# LevelShifting_Isolation.net
KiCad netlist of a schematic drawn in Altium Designer
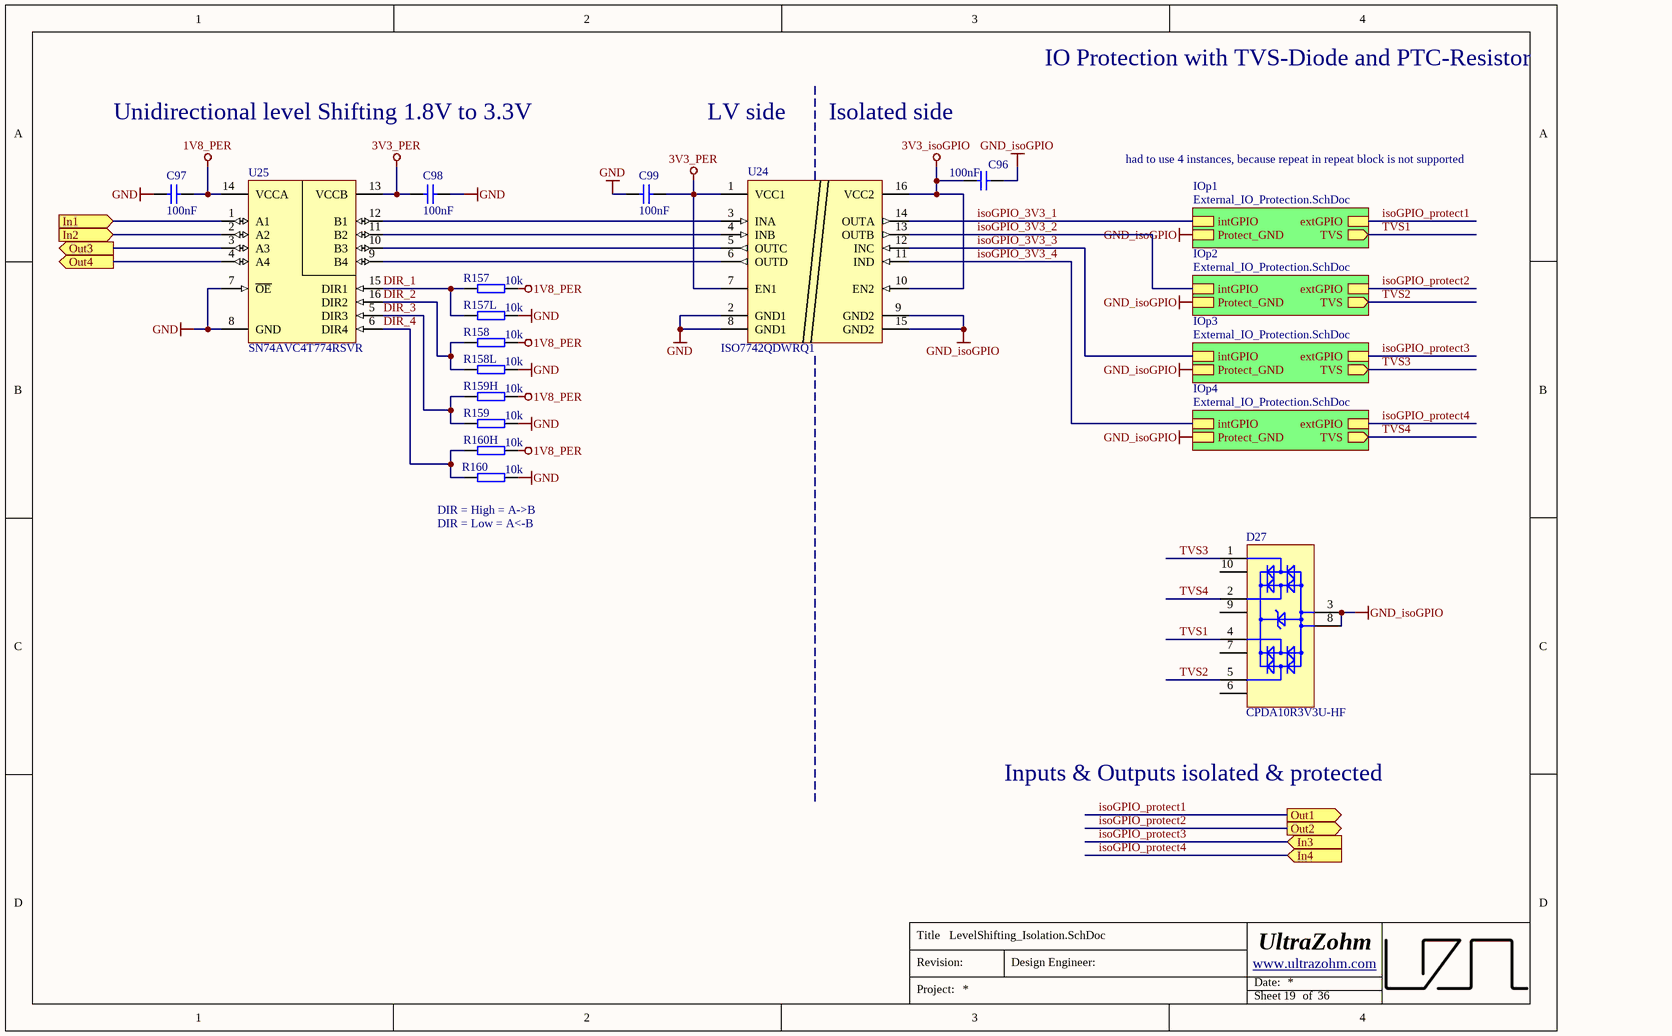
[diagram p0: LevelShifting_Isolation.SchDoc]

(export (version "E")
  (design (tool "Eeschema 10.0.6"))
  (components
    (comp (ref "C96")
      (value "100nF")
      (footprint "CAPC1608X90N_V")
      (description "KON 100nF 50V X7R ±10% SMD BF 1608 (0603)")
      (fields (field (name "TOLERANCE") "±10%") (field (name "VOLTAGE") "50V"))
      (libsource (lib "TE") (part "CAP-NP"))
    )
    (comp (ref "C97")
      (value "100nF")
      (footprint "CAPC1608X90N_V")
      (description "KON 100nF 50V X7R ±10% SMD BF 1608 (0603)")
      (fields (field (name "TOLERANCE") "±10%") (field (name "VOLTAGE") "50V"))
      (libsource (lib "TE") (part "CAP-NP"))
    )
    (comp (ref "C98")
      (value "100nF")
      (footprint "CAPC1608X90N_V")
      (description "KON 100nF 50V X7R ±10% SMD BF 1608 (0603)")
      (fields (field (name "TOLERANCE") "±10%") (field (name "VOLTAGE") "50V"))
      (libsource (lib "TE") (part "CAP-NP"))
    )
    (comp (ref "C99")
      (value "100nF")
      (footprint "CAPC1608X90N_V")
      (description "KON 100nF 50V X7R ±10% SMD BF 1608 (0603)")
      (fields (field (name "TOLERANCE") "±10%") (field (name "VOLTAGE") "50V"))
      (libsource (lib "TE") (part "CAP-NP"))
    )
    (comp (ref "D27")
      (value "CPDA10R3V3U-HF")
      (footprint "DFN230X100X55X10N")
      (fields (field (name "VOLTAGE") "3.3V"))
      (libsource (lib "TE") (part "DIODE_ARR_10N_1"))
    )
    (comp (ref "R157")
      (value "10k")
      (footprint "R_0603_TE")
      (description "Generic resistor")
      (fields
        (field (name "TOLERANCE") "1 %")
        (field (name "MANUFACTURER PART NUMBER") "UZgen_R_0603_10k")
        (field (name "CREATED FROM") "AGeiger")
      )
      (libsource (lib "user") (part "RES"))
    )
    (comp (ref "R157L")
      (value "10k")
      (footprint "R_0603_TE")
      (description "Generic resistor")
      (fields
        (field (name "TOLERANCE") "1 %")
        (field (name "MANUFACTURER PART NUMBER") "UZgen_R_0603_10k")
        (field (name "CREATED FROM") "AGeiger")
      )
      (libsource (lib "user") (part "RES"))
    )
    (comp (ref "R158")
      (value "10k")
      (footprint "R_0603_TE")
      (description "Generic resistor")
      (fields
        (field (name "TOLERANCE") "1 %")
        (field (name "MANUFACTURER PART NUMBER") "UZgen_R_0603_10k")
        (field (name "CREATED FROM") "AGeiger")
      )
      (libsource (lib "user") (part "RES"))
    )
    (comp (ref "R158L")
      (value "10k")
      (footprint "R_0603_TE")
      (description "Generic resistor")
      (fields
        (field (name "TOLERANCE") "1 %")
        (field (name "MANUFACTURER PART NUMBER") "UZgen_R_0603_10k")
        (field (name "CREATED FROM") "AGeiger")
      )
      (libsource (lib "user") (part "RES"))
    )
    (comp (ref "R159")
      (value "10k")
      (footprint "R_0603_TE")
      (description "Generic resistor")
      (fields
        (field (name "TOLERANCE") "1 %")
        (field (name "MANUFACTURER PART NUMBER") "UZgen_R_0603_10k")
        (field (name "CREATED FROM") "AGeiger")
      )
      (libsource (lib "user") (part "RES"))
    )
    (comp (ref "R159H")
      (value "10k")
      (footprint "R_0603_TE")
      (description "Generic resistor")
      (fields
        (field (name "TOLERANCE") "1 %")
        (field (name "MANUFACTURER PART NUMBER") "UZgen_R_0603_10k")
        (field (name "CREATED FROM") "AGeiger")
      )
      (libsource (lib "user") (part "RES"))
    )
    (comp (ref "R160")
      (value "10k")
      (footprint "R_0603_TE")
      (description "Generic resistor")
      (fields
        (field (name "TOLERANCE") "1 %")
        (field (name "MANUFACTURER PART NUMBER") "UZgen_R_0603_10k")
        (field (name "CREATED FROM") "AGeiger")
      )
      (libsource (lib "user") (part "RES"))
    )
    (comp (ref "R160H")
      (value "10k")
      (footprint "R_0603_TE")
      (description "Generic resistor")
      (fields
        (field (name "TOLERANCE") "1 %")
        (field (name "MANUFACTURER PART NUMBER") "UZgen_R_0603_10k")
        (field (name "CREATED FROM") "AGeiger")
      )
      (libsource (lib "user") (part "RES"))
    )
    (comp (ref "U24")
      (value "ISO7742QDWRQ1")
      (footprint "SOIC127P1030X265-16N")
      (libsource (lib "TE") (part "ISO7742"))
    )
    (comp (ref "U25")
      (value "SN74AVC4T774RSVR")
      (footprint "QFN40P260X180X55-16N")
      (libsource (lib "TE") (part "SN74AVC4T774RSVR"))
    )
  )
  (nets
    (net (code "2") (name "/DIR_1") (class "Default")
      (node (ref "R157") (pin "1") (pinfunction "1_1") (pintype "passive"))
      (node (ref "R157L") (pin "1") (pinfunction "1_1") (pintype "passive"))
      (node (ref "U25") (pin "15") (pinfunction "DIR1_15") (pintype "input"))
    )
    (net (code "3") (name "/DIR_2") (class "Default")
      (node (ref "R158") (pin "1") (pinfunction "1_1") (pintype "passive"))
      (node (ref "R158L") (pin "1") (pinfunction "1_1") (pintype "passive"))
      (node (ref "U25") (pin "16") (pinfunction "DIR2_16") (pintype "input"))
    )
    (net (code "4") (name "/DIR_3") (class "Default")
      (node (ref "R159") (pin "1") (pinfunction "1_1") (pintype "passive"))
      (node (ref "R159H") (pin "1") (pinfunction "1_1") (pintype "passive"))
      (node (ref "U25") (pin "5") (pinfunction "DIR3_5") (pintype "input"))
    )
    (net (code "5") (name "/DIR_4") (class "Default")
      (node (ref "R160") (pin "1") (pinfunction "1_1") (pintype "passive"))
      (node (ref "R160H") (pin "1") (pinfunction "1_1") (pintype "passive"))
      (node (ref "U25") (pin "6") (pinfunction "DIR4_6") (pintype "input"))
    )
    (net (code "6") (name "/In1") (class "Default")
      (node (ref "U25") (pin "1") (pinfunction "A1_1") (pintype "bidirectional"))
    )
    (net (code "7") (name "/In2") (class "Default")
      (node (ref "U25") (pin "2") (pinfunction "A2_2") (pintype "bidirectional"))
    )
    (net (code "8") (name "/Out3") (class "Default")
      (node (ref "U25") (pin "3") (pinfunction "A3_3") (pintype "bidirectional"))
    )
    (net (code "9") (name "/Out4") (class "Default")
      (node (ref "U25") (pin "4") (pinfunction "A4_4") (pintype "bidirectional"))
    )
    (net (code "10") (name "/TVS1") (class "Default")
      (node (ref "D27") (pin "4") (pinfunction "4_4") (pintype "passive"))
    )
    (net (code "11") (name "/TVS2") (class "Default")
      (node (ref "D27") (pin "5") (pinfunction "5_5") (pintype "passive"))
    )
    (net (code "12") (name "/TVS3") (class "Default")
      (node (ref "D27") (pin "1") (pinfunction "1_1") (pintype "passive"))
    )
    (net (code "13") (name "/TVS4") (class "Default")
      (node (ref "D27") (pin "2") (pinfunction "2_2") (pintype "passive"))
    )
    (net (code "14") (name "/isoGPIO_3V3_1") (class "Default")
      (node (ref "U24") (pin "14") (pinfunction "OUTA_14") (pintype "output"))
    )
    (net (code "15") (name "/isoGPIO_3V3_2") (class "Default")
      (node (ref "U24") (pin "13") (pinfunction "OUTB_13") (pintype "output"))
    )
    (net (code "16") (name "/isoGPIO_3V3_3") (class "Default")
      (node (ref "U24") (pin "12") (pinfunction "INC_12") (pintype "input"))
    )
    (net (code "17") (name "/isoGPIO_3V3_4") (class "Default")
      (node (ref "U24") (pin "11") (pinfunction "IND_11") (pintype "input"))
    )
    (net (code "22") (name "1V8_PER") (class "Default")
      (node (ref "C97") (pin "1") (pinfunction "1_1") (pintype "passive"))
      (node (ref "R157") (pin "2") (pinfunction "2_2") (pintype "passive"))
      (node (ref "R158") (pin "2") (pinfunction "2_2") (pintype "passive"))
      (node (ref "R159H") (pin "2") (pinfunction "2_2") (pintype "passive"))
      (node (ref "R160H") (pin "2") (pinfunction "2_2") (pintype "passive"))
      (node (ref "U25") (pin "14") (pinfunction "VCCA_14") (pintype "power_in"))
    )
    (net (code "23") (name "3V3_PER") (class "Default")
      (node (ref "C98") (pin "2") (pinfunction "2_2") (pintype "passive"))
      (node (ref "C99") (pin "2") (pinfunction "2_2") (pintype "passive"))
      (node (ref "U24") (pin "1") (pinfunction "VCC1_1") (pintype "power_in"))
      (node (ref "U24") (pin "7") (pinfunction "EN1_7") (pintype "passive"))
      (node (ref "U25") (pin "13") (pinfunction "VCCB_13") (pintype "power_in"))
    )
    (net (code "24") (name "3V3_isoGPIO") (class "Default")
      (node (ref "C96") (pin "1") (pinfunction "1_1") (pintype "passive"))
      (node (ref "U24") (pin "10") (pinfunction "EN2_10") (pintype "input"))
      (node (ref "U24") (pin "16") (pinfunction "VCC2_16") (pintype "power_in"))
    )
    (net (code "25") (name "GND") (class "Default")
      (node (ref "C97") (pin "2") (pinfunction "2_2") (pintype "passive"))
      (node (ref "C98") (pin "1") (pinfunction "1_1") (pintype "passive"))
      (node (ref "C99") (pin "1") (pinfunction "1_1") (pintype "passive"))
      (node (ref "R157L") (pin "2") (pinfunction "2_2") (pintype "passive"))
      (node (ref "R158L") (pin "2") (pinfunction "2_2") (pintype "passive"))
      (node (ref "R159") (pin "2") (pinfunction "2_2") (pintype "passive"))
      (node (ref "R160") (pin "2") (pinfunction "2_2") (pintype "passive"))
      (node (ref "U24") (pin "2") (pinfunction "GND1_2") (pintype "power_in"))
      (node (ref "U24") (pin "8") (pinfunction "GND1_8") (pintype "power_in"))
      (node (ref "U25") (pin "7") (pinfunction "~{OE}_7") (pintype "input"))
      (node (ref "U25") (pin "8") (pinfunction "GND_8") (pintype "power_in"))
    )
    (net (code "26") (name "GND_isoGPIO") (class "Default")
      (node (ref "C96") (pin "2") (pinfunction "2_2") (pintype "passive"))
      (node (ref "D27") (pin "3") (pinfunction "3_3") (pintype "passive"))
      (node (ref "D27") (pin "8") (pinfunction "8_8") (pintype "passive"))
      (node (ref "U24") (pin "15") (pinfunction "GND2_15") (pintype "power_in"))
      (node (ref "U24") (pin "9") (pinfunction "GND2_9") (pintype "power_in"))
    )
    (net (code "27") (name "Net-(U24-INA)") (class "Default")
      (node (ref "U24") (pin "3") (pinfunction "INA_3") (pintype "input"))
      (node (ref "U25") (pin "12") (pinfunction "B1_12") (pintype "bidirectional"))
    )
    (net (code "28") (name "Net-(U24-INB)") (class "Default")
      (node (ref "U24") (pin "4") (pinfunction "INB_4") (pintype "input"))
      (node (ref "U25") (pin "11") (pinfunction "B2_11") (pintype "bidirectional"))
    )
    (net (code "29") (name "Net-(U24-OUTC)") (class "Default")
      (node (ref "U24") (pin "5") (pinfunction "OUTC_5") (pintype "output"))
      (node (ref "U25") (pin "10") (pinfunction "B3_10") (pintype "bidirectional"))
    )
    (net (code "30") (name "Net-(U24-OUTD)") (class "Default")
      (node (ref "U24") (pin "6") (pinfunction "OUTD_6") (pintype "output"))
      (node (ref "U25") (pin "9") (pinfunction "B4_9") (pintype "bidirectional"))
    )
    (net (code "31") (name "unconnected-(D27-Pad6)") (class "Default")
      (node (ref "D27") (pin "6") (pinfunction "6_6") (pintype "passive"))
    )
    (net (code "32") (name "unconnected-(D27-Pad7)") (class "Default")
      (node (ref "D27") (pin "7") (pinfunction "7_7") (pintype "passive"))
    )
    (net (code "33") (name "unconnected-(D27-Pad9)") (class "Default")
      (node (ref "D27") (pin "9") (pinfunction "9_9") (pintype "passive"))
    )
    (net (code "34") (name "unconnected-(D27-Pad10)") (class "Default")
      (node (ref "D27") (pin "10") (pinfunction "10_10") (pintype "passive"))
    )
  )
)
